# OMD_CAN_VERT.net
KiCad netlist of a schematic drawn in Altium Designer
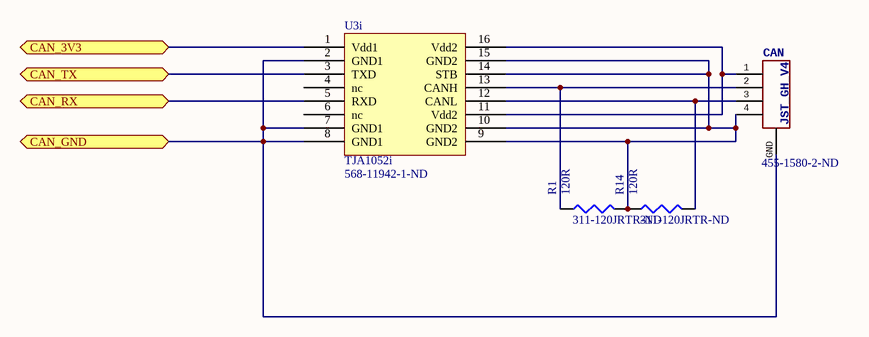
[diagram p0: OMD_CAN_VERT.SchDoc]

(export (version "E")
  (design (tool "Eeschema 10.0.6"))
  (components
    (comp (ref "CAN")
      (value "JST_GH_V4")
      (footprint "JST_GH_V4")
      (description "BM04B-GHS-TBT")
      (fields (field (name "SUPPLIER PART NUMBER 1") "455-1580-2-ND"))
      (libsource (lib "CB_SCI_AERO") (part "JST_GH_V4"))
    )
    (comp (ref "R1")
      (value "120R")
      (footprint "R0402")
      (description "RES SMD 120 OHM 5% 1/16W 0402")
      (fields (field (name "SUPPLIER PART NUMBER 1") "311-120JRTR-ND"))
      (libsource (lib "OMD") (part "Resistor"))
    )
    (comp (ref "R14")
      (value "120R")
      (footprint "R0402")
      (description "RES SMD 120 OHM 5% 1/16W 0402")
      (fields (field (name "SUPPLIER PART NUMBER 1") "311-120JRTR-ND"))
      (libsource (lib "OMD") (part "Resistor"))
    )
    (comp (ref "U3i")
      (value "TJA1052i")
      (footprint "TJA1052i")
      (fields (field (name "SUPPLIER PART NUMBER 1") "568-11942-1-ND"))
      (libsource (lib "OMD") (part "TJA1052i"))
    )
  )
  (nets
    (net (code "1") (name "/CAN_3V3") (class "Default")
      (node (ref "U3i") (pin "1") (pinfunction "Vdd1_1") (pintype "passive"))
    )
    (net (code "2") (name "/CAN_GND") (class "Default")
      (node (ref "CAN") (pin "GND") (pinfunction "GND_GND") (pintype "passive"))
      (node (ref "U3i") (pin "2") (pinfunction "GND1_2") (pintype "passive"))
      (node (ref "U3i") (pin "7") (pinfunction "GND1_7") (pintype "passive"))
      (node (ref "U3i") (pin "8") (pinfunction "GND1_8") (pintype "passive"))
    )
    (net (code "3") (name "/CAN_RX") (class "Default")
      (node (ref "U3i") (pin "5") (pinfunction "RXD_5") (pintype "passive"))
    )
    (net (code "4") (name "/CAN_TX") (class "Default")
      (node (ref "U3i") (pin "3") (pinfunction "TXD_3") (pintype "passive"))
    )
    (net (code "5") (name "Net-(CAN-Pad1)") (class "Default")
      (node (ref "CAN") (pin "1") (pinfunction "1_1") (pintype "passive"))
      (node (ref "U3i") (pin "11") (pinfunction "Vdd2_11") (pintype "passive"))
      (node (ref "U3i") (pin "16") (pinfunction "Vdd2_16") (pintype "passive"))
    )
    (net (code "6") (name "Net-(U3i-CANH)") (class "Default")
      (node (ref "CAN") (pin "2") (pinfunction "2_2") (pintype "passive"))
      (node (ref "R1") (pin "1") (pinfunction "1_1") (pintype "passive"))
      (node (ref "U3i") (pin "13") (pinfunction "CANH_13") (pintype "passive"))
    )
    (net (code "7") (name "Net-(U3i-CANL)") (class "Default")
      (node (ref "CAN") (pin "3") (pinfunction "3_3") (pintype "passive"))
      (node (ref "R14") (pin "2") (pinfunction "2_2") (pintype "passive"))
      (node (ref "U3i") (pin "12") (pinfunction "CANL_12") (pintype "passive"))
    )
    (net (code "8") (name "Net-(U3i-STB)") (class "Default")
      (node (ref "CAN") (pin "4") (pinfunction "4_4") (pintype "passive"))
      (node (ref "R1") (pin "2") (pinfunction "2_2") (pintype "passive"))
      (node (ref "R14") (pin "1") (pinfunction "1_1") (pintype "passive"))
      (node (ref "U3i") (pin "10") (pinfunction "GND2_10") (pintype "passive"))
      (node (ref "U3i") (pin "14") (pinfunction "STB_14") (pintype "passive"))
      (node (ref "U3i") (pin "15") (pinfunction "GND2_15") (pintype "passive"))
      (node (ref "U3i") (pin "9") (pinfunction "GND2_9") (pintype "passive"))
    )
    (net (code "9") (name "unconnected-(U3i-nc-Pad4)") (class "Default")
      (node (ref "U3i") (pin "4") (pinfunction "nc_4") (pintype "passive"))
    )
    (net (code "10") (name "unconnected-(U3i-nc-Pad6)") (class "Default")
      (node (ref "U3i") (pin "6") (pinfunction "nc_6") (pintype "passive"))
    )
  )
)
